# p0rx-001.net
KiCad netlist of a schematic drawn in EAGLE
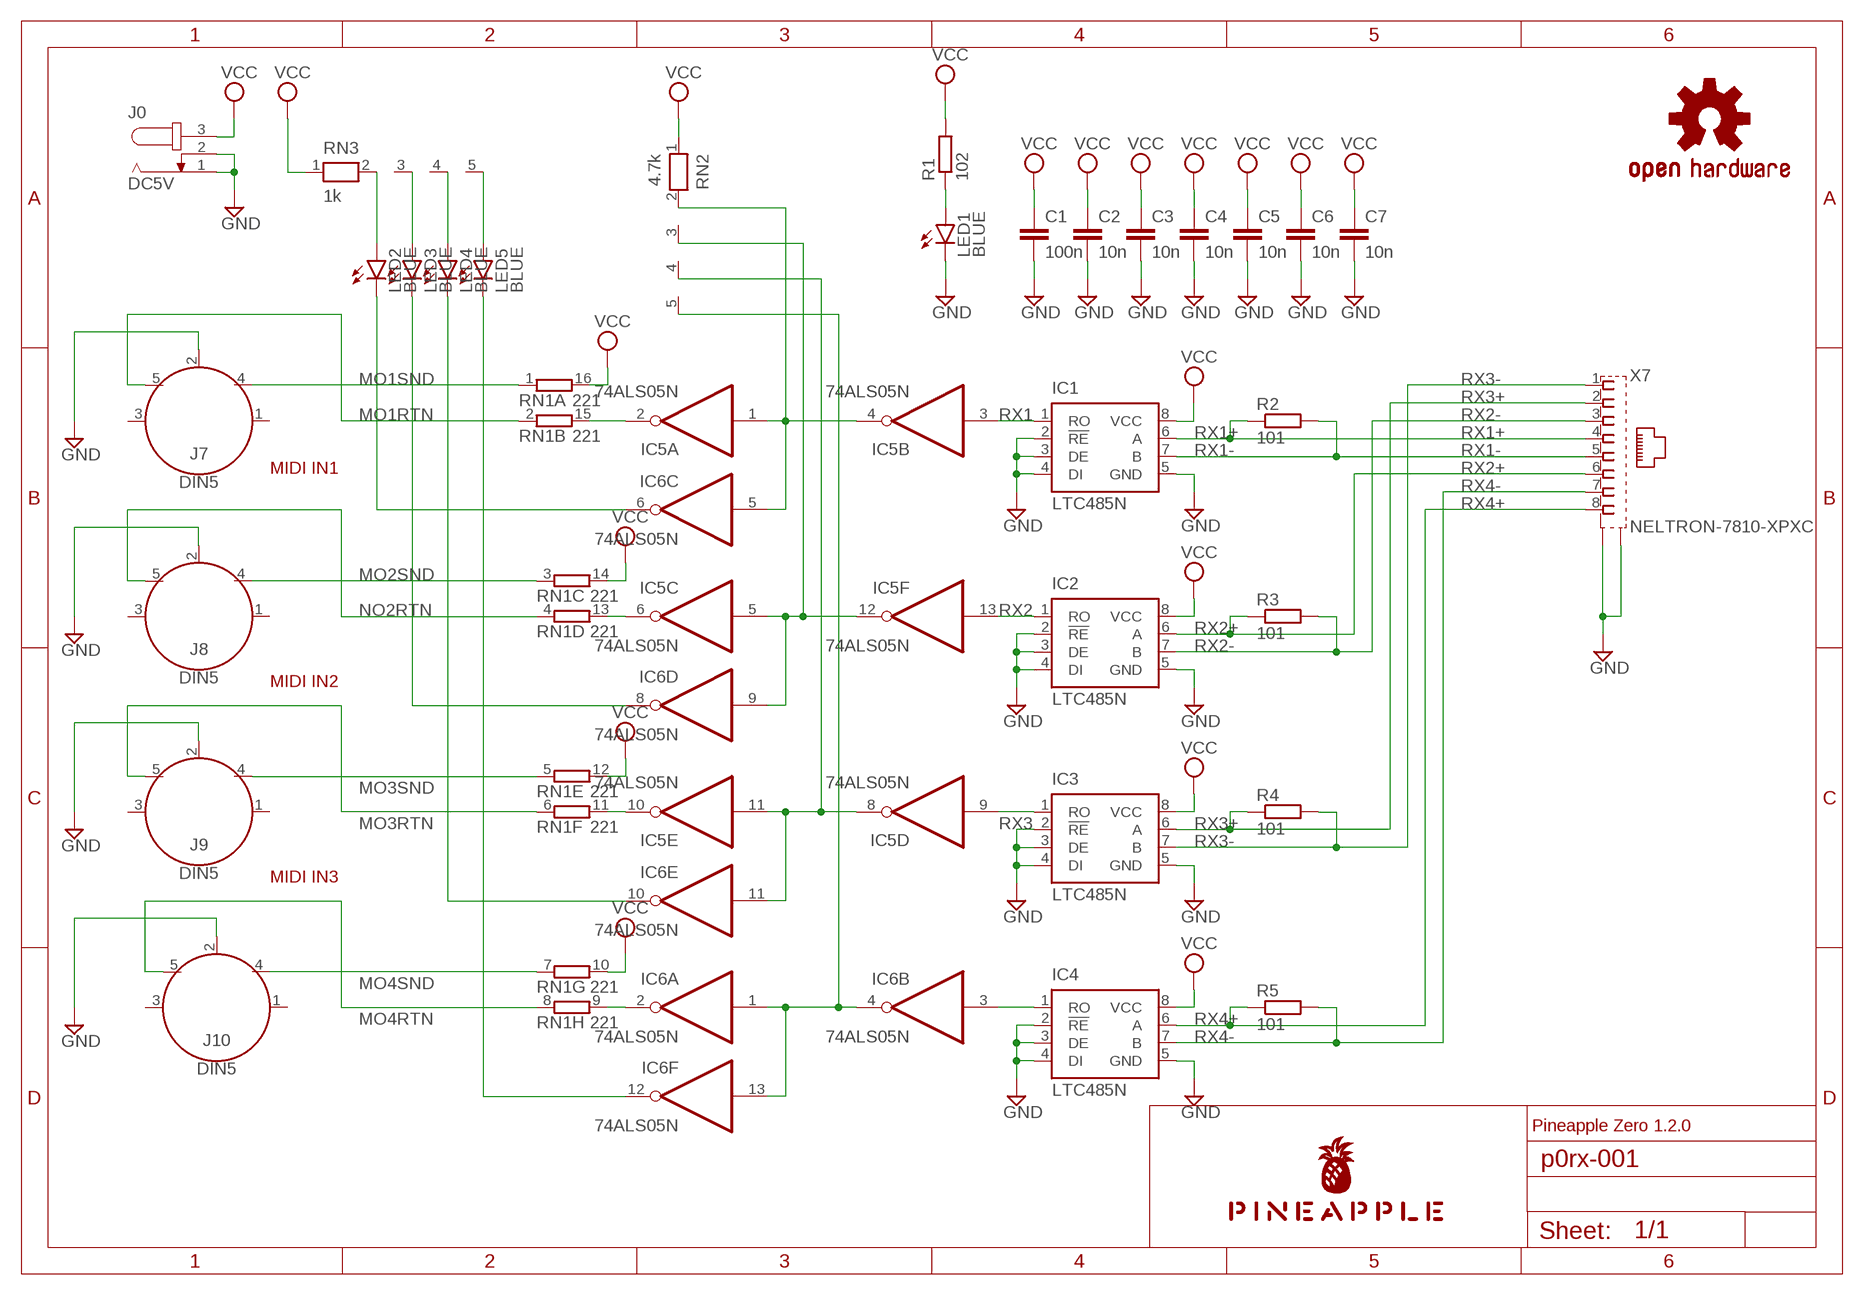
[diagram p0: schematic, sheet 1]

(export (version "E")
  (design (tool "Eeschema 10.0.6"))
  (components
    (comp (ref "C1")
      (value "100n")
      (footprint "eagle-import:C025-024X044")
      (libsource (lib "eagle-import") (part "C-EU025-024X044"))
    )
    (comp (ref "C2")
      (value "10n")
      (footprint "eagle-import:C025-024X044")
      (libsource (lib "eagle-import") (part "C-EU025-024X044"))
    )
    (comp (ref "C3")
      (value "10n")
      (footprint "eagle-import:C025-024X044")
      (libsource (lib "eagle-import") (part "C-EU025-024X044"))
    )
    (comp (ref "C4")
      (value "10n")
      (footprint "eagle-import:C025-024X044")
      (libsource (lib "eagle-import") (part "C-EU025-024X044"))
    )
    (comp (ref "C5")
      (value "10n")
      (footprint "eagle-import:C025-024X044")
      (libsource (lib "eagle-import") (part "C-EU025-024X044"))
    )
    (comp (ref "C6")
      (value "10n")
      (footprint "eagle-import:C025-024X044")
      (libsource (lib "eagle-import") (part "C-EU025-024X044"))
    )
    (comp (ref "C7")
      (value "10n")
      (footprint "eagle-import:C025-024X044")
      (libsource (lib "eagle-import") (part "C-EU025-024X044"))
    )
    (comp (ref "IC1")
      (value "LTC485N")
      (footprint "eagle-import:DIL08")
      (libsource (lib "eagle-import") (part "LTC485N"))
    )
    (comp (ref "IC2")
      (value "LTC485N")
      (footprint "eagle-import:DIL08")
      (libsource (lib "eagle-import") (part "LTC485N"))
    )
    (comp (ref "IC3")
      (value "LTC485N")
      (footprint "eagle-import:DIL08")
      (libsource (lib "eagle-import") (part "LTC485N"))
    )
    (comp (ref "IC4")
      (value "LTC485N")
      (footprint "eagle-import:DIL08")
      (libsource (lib "eagle-import") (part "LTC485N"))
    )
    (comp (ref "IC5")
      (value "74ALS05N")
      (footprint "eagle-import:DIL14")
      (libsource (lib "eagle-import") (part "7405NALS"))
    )
    (comp (ref "IC6")
      (value "74ALS05N")
      (footprint "eagle-import:DIL14")
      (libsource (lib "eagle-import") (part "7405NALS"))
    )
    (comp (ref "J0")
      (value "DC5V")
      (footprint "eagle-import:SPC4077")
      (libsource (lib "eagle-import") (part "JACK-PLUG0"))
    )
    (comp (ref "J7")
      (value "DIN5")
      (footprint "eagle-import:DIN5-RA-PTH")
      (libsource (lib "eagle-import") (part "DIN5"))
    )
    (comp (ref "J8")
      (value "DIN5")
      (footprint "eagle-import:DIN5-RA-PTH")
      (libsource (lib "eagle-import") (part "DIN5"))
    )
    (comp (ref "J9")
      (value "DIN5")
      (footprint "eagle-import:DIN5-RA-PTH")
      (libsource (lib "eagle-import") (part "DIN5"))
    )
    (comp (ref "J10")
      (value "DIN5")
      (footprint "eagle-import:DIN5-RA-PTH")
      (libsource (lib "eagle-import") (part "DIN5"))
    )
    (comp (ref "LED1")
      (value "BLUE")
      (footprint "eagle-import:LED3MM")
      (libsource (lib "eagle-import") (part "LED3MM"))
    )
    (comp (ref "LED2")
      (value "BLUE")
      (footprint "eagle-import:LED3MM")
      (libsource (lib "eagle-import") (part "LED3MM"))
    )
    (comp (ref "LED3")
      (value "BLUE")
      (footprint "eagle-import:LED3MM")
      (libsource (lib "eagle-import") (part "LED3MM"))
    )
    (comp (ref "LED4")
      (value "BLUE")
      (footprint "eagle-import:LED3MM")
      (libsource (lib "eagle-import") (part "LED3MM"))
    )
    (comp (ref "LED5")
      (value "BLUE")
      (footprint "eagle-import:LED3MM")
      (libsource (lib "eagle-import") (part "LED3MM"))
    )
    (comp (ref "LOGO1")
      (value "OSHW-LOGOS-COPPER")
      (footprint "eagle-import:OSHW-LOGO-S_COPPER")
      (libsource (lib "eagle-import") (part "OSHW-LOGOS-COPPER"))
    )
    (comp (ref "R1")
      (value "102")
      (footprint "eagle-import:0204_5")
      (libsource (lib "eagle-import") (part "R-EU_0204/5"))
    )
    (comp (ref "R2")
      (value "101")
      (footprint "eagle-import:0204_5")
      (libsource (lib "eagle-import") (part "R-EU_0204/5"))
    )
    (comp (ref "R3")
      (value "101")
      (footprint "eagle-import:0204_5")
      (libsource (lib "eagle-import") (part "R-EU_0204/5"))
    )
    (comp (ref "R4")
      (value "101")
      (footprint "eagle-import:0204_5")
      (libsource (lib "eagle-import") (part "R-EU_0204/5"))
    )
    (comp (ref "R5")
      (value "101")
      (footprint "eagle-import:0204_5")
      (libsource (lib "eagle-import") (part "R-EU_0204/5"))
    )
    (comp (ref "RN1")
      (value "221")
      (footprint "eagle-import:DIL16")
      (libsource (lib "eagle-import") (part "8R-N"))
    )
    (comp (ref "RN2")
      (value "4.7k")
      (footprint "eagle-import:RN-5")
      (libsource (lib "eagle-import") (part "RN04"))
    )
    (comp (ref "RN3")
      (value "1k")
      (footprint "eagle-import:RN-5")
      (libsource (lib "eagle-import") (part "RN04"))
    )
    (comp (ref "U$1")
      (value "PINEAPPLE450")
      (footprint "eagle-import:PINEAPPLE450")
      (libsource (lib "eagle-import") (part "PINEAPPLE450"))
    )
    (comp (ref "X7")
      (value "NELTRON-7810-XPXC")
      (footprint "eagle-import:NELTRON-7810-XPXC-FOOTPRINT")
      (libsource (lib "eagle-import") (part "NELTRON-7810-XPXC"))
    )
  )
  (nets
    (net (code "1") (name "/MO1RTN") (class "Default")
      (node (ref "J7") (pin "5") (pinfunction "5_5") (pintype "bidirectional"))
      (node (ref "RN1") (pin "2") (pinfunction "1_2") (pintype "passive"))
    )
    (net (code "2") (name "/MO1SND") (class "Default")
      (node (ref "J7") (pin "4") (pinfunction "4_4") (pintype "bidirectional"))
      (node (ref "RN1") (pin "1") (pinfunction "1_1") (pintype "passive"))
    )
    (net (code "3") (name "/MO2SND") (class "Default")
      (node (ref "J8") (pin "4") (pinfunction "4_4") (pintype "bidirectional"))
      (node (ref "RN1") (pin "3") (pinfunction "1_3") (pintype "passive"))
    )
    (net (code "4") (name "/MO3RTN") (class "Default")
      (node (ref "J9") (pin "5") (pinfunction "5_5") (pintype "bidirectional"))
      (node (ref "RN1") (pin "6") (pinfunction "1_6") (pintype "passive"))
    )
    (net (code "5") (name "/MO3SND") (class "Default")
      (node (ref "J9") (pin "4") (pinfunction "4_4") (pintype "bidirectional"))
      (node (ref "RN1") (pin "5") (pinfunction "1_5") (pintype "passive"))
    )
    (net (code "6") (name "/MO4RTN") (class "Default")
      (node (ref "J10") (pin "5") (pinfunction "5_5") (pintype "bidirectional"))
      (node (ref "RN1") (pin "8") (pinfunction "1_8") (pintype "passive"))
    )
    (net (code "7") (name "/MO4SND") (class "Default")
      (node (ref "J10") (pin "4") (pinfunction "4_4") (pintype "bidirectional"))
      (node (ref "RN1") (pin "7") (pinfunction "1_7") (pintype "passive"))
    )
    (net (code "8") (name "/NO2RTN") (class "Default")
      (node (ref "J8") (pin "5") (pinfunction "5_5") (pintype "bidirectional"))
      (node (ref "RN1") (pin "4") (pinfunction "1_4") (pintype "passive"))
    )
    (net (code "9") (name "/RX1") (class "Default")
      (node (ref "IC1") (pin "1") (pinfunction "RO_1") (pintype "output"))
      (node (ref "IC5") (pin "3") (pinfunction "I_3") (pintype "input"))
    )
    (net (code "10") (name "/RX1+") (class "Default")
      (node (ref "IC1") (pin "6") (pinfunction "A_6") (pintype "bidirectional"))
      (node (ref "R2") (pin "1") (pinfunction "1_1") (pintype "passive"))
      (node (ref "X7") (pin "4") (pinfunction "4_4") (pintype "passive"))
    )
    (net (code "11") (name "/RX1-") (class "Default")
      (node (ref "IC1") (pin "7") (pinfunction "B_7") (pintype "bidirectional"))
      (node (ref "R2") (pin "2") (pinfunction "2_2") (pintype "passive"))
      (node (ref "X7") (pin "5") (pinfunction "5_5") (pintype "passive"))
    )
    (net (code "12") (name "/RX2") (class "Default")
      (node (ref "IC2") (pin "1") (pinfunction "RO_1") (pintype "output"))
      (node (ref "IC5") (pin "13") (pinfunction "I_13") (pintype "input"))
    )
    (net (code "13") (name "/RX2+") (class "Default")
      (node (ref "IC2") (pin "6") (pinfunction "A_6") (pintype "bidirectional"))
      (node (ref "R3") (pin "1") (pinfunction "1_1") (pintype "passive"))
      (node (ref "X7") (pin "6") (pinfunction "6_6") (pintype "passive"))
    )
    (net (code "14") (name "/RX2-") (class "Default")
      (node (ref "IC2") (pin "7") (pinfunction "B_7") (pintype "bidirectional"))
      (node (ref "R3") (pin "2") (pinfunction "2_2") (pintype "passive"))
      (node (ref "X7") (pin "3") (pinfunction "3_3") (pintype "passive"))
    )
    (net (code "15") (name "/RX3") (class "Default")
      (node (ref "IC3") (pin "1") (pinfunction "RO_1") (pintype "output"))
      (node (ref "IC5") (pin "9") (pinfunction "I_9") (pintype "input"))
    )
    (net (code "16") (name "/RX3+") (class "Default")
      (node (ref "IC3") (pin "6") (pinfunction "A_6") (pintype "bidirectional"))
      (node (ref "R4") (pin "1") (pinfunction "1_1") (pintype "passive"))
      (node (ref "X7") (pin "2") (pinfunction "2_2") (pintype "passive"))
    )
    (net (code "17") (name "/RX3-") (class "Default")
      (node (ref "IC3") (pin "7") (pinfunction "B_7") (pintype "bidirectional"))
      (node (ref "R4") (pin "2") (pinfunction "2_2") (pintype "passive"))
      (node (ref "X7") (pin "1") (pinfunction "1_1") (pintype "passive"))
    )
    (net (code "18") (name "/RX4+") (class "Default")
      (node (ref "IC4") (pin "6") (pinfunction "A_6") (pintype "bidirectional"))
      (node (ref "R5") (pin "1") (pinfunction "1_1") (pintype "passive"))
      (node (ref "X7") (pin "8") (pinfunction "8_8") (pintype "passive"))
    )
    (net (code "19") (name "/RX4-") (class "Default")
      (node (ref "IC4") (pin "7") (pinfunction "B_7") (pintype "bidirectional"))
      (node (ref "R5") (pin "2") (pinfunction "2_2") (pintype "passive"))
      (node (ref "X7") (pin "7") (pinfunction "7_7") (pintype "passive"))
    )
    (net (code "20") (name "GND") (class "Default")
      (node (ref "C1") (pin "2") (pinfunction "2_2") (pintype "passive"))
      (node (ref "C2") (pin "2") (pinfunction "2_2") (pintype "passive"))
      (node (ref "C3") (pin "2") (pinfunction "2_2") (pintype "passive"))
      (node (ref "C4") (pin "2") (pinfunction "2_2") (pintype "passive"))
      (node (ref "C5") (pin "2") (pinfunction "2_2") (pintype "passive"))
      (node (ref "C6") (pin "2") (pinfunction "2_2") (pintype "passive"))
      (node (ref "C7") (pin "2") (pinfunction "2_2") (pintype "passive"))
      (node (ref "IC1") (pin "2") (pinfunction "~{RE}_2") (pintype "input"))
      (node (ref "IC1") (pin "3") (pinfunction "DE_3") (pintype "input"))
      (node (ref "IC1") (pin "4") (pinfunction "DI_4") (pintype "input"))
      (node (ref "IC1") (pin "5") (pinfunction "GND_5") (pintype "input"))
      (node (ref "IC2") (pin "2") (pinfunction "~{RE}_2") (pintype "input"))
      (node (ref "IC2") (pin "3") (pinfunction "DE_3") (pintype "input"))
      (node (ref "IC2") (pin "4") (pinfunction "DI_4") (pintype "input"))
      (node (ref "IC2") (pin "5") (pinfunction "GND_5") (pintype "input"))
      (node (ref "IC3") (pin "2") (pinfunction "~{RE}_2") (pintype "input"))
      (node (ref "IC3") (pin "3") (pinfunction "DE_3") (pintype "input"))
      (node (ref "IC3") (pin "4") (pinfunction "DI_4") (pintype "input"))
      (node (ref "IC3") (pin "5") (pinfunction "GND_5") (pintype "input"))
      (node (ref "IC4") (pin "2") (pinfunction "~{RE}_2") (pintype "input"))
      (node (ref "IC4") (pin "3") (pinfunction "DE_3") (pintype "input"))
      (node (ref "IC4") (pin "4") (pinfunction "DI_4") (pintype "input"))
      (node (ref "IC4") (pin "5") (pinfunction "GND_5") (pintype "input"))
      (node (ref "J0") (pin "1") (pinfunction "1_1") (pintype "passive"))
      (node (ref "J0") (pin "2") (pinfunction "2_2") (pintype "passive"))
      (node (ref "J10") (pin "2") (pinfunction "2_2") (pintype "bidirectional"))
      (node (ref "J7") (pin "2") (pinfunction "2_2") (pintype "bidirectional"))
      (node (ref "J8") (pin "2") (pinfunction "2_2") (pintype "bidirectional"))
      (node (ref "J9") (pin "2") (pinfunction "2_2") (pintype "bidirectional"))
      (node (ref "LED1") (pin "K") (pinfunction "C_K") (pintype "passive"))
      (node (ref "X7") (pin "S1") (pinfunction "S1_S1") (pintype "passive"))
      (node (ref "X7") (pin "S2") (pinfunction "S2_S2") (pintype "passive"))
    )
    (net (code "21") (name "Net-(IC4-RO)") (class "Default")
      (node (ref "IC4") (pin "1") (pinfunction "RO_1") (pintype "output"))
      (node (ref "IC6") (pin "3") (pinfunction "I_3") (pintype "input"))
    )
    (net (code "22") (name "Net-(IC5A-I)") (class "Default")
      (node (ref "IC5") (pin "1") (pinfunction "I_1") (pintype "input"))
      (node (ref "IC5") (pin "4") (pinfunction "O_4") (pintype "open_collector"))
      (node (ref "IC6") (pin "5") (pinfunction "I_5") (pintype "input"))
      (node (ref "RN2") (pin "2") (pinfunction "2_2") (pintype "passive"))
    )
    (net (code "23") (name "Net-(IC5A-O)") (class "Default")
      (node (ref "IC5") (pin "2") (pinfunction "O_2") (pintype "open_collector"))
      (node (ref "RN1") (pin "15") (pinfunction "2_15") (pintype "passive"))
    )
    (net (code "24") (name "Net-(IC5C-I)") (class "Default")
      (node (ref "IC5") (pin "12") (pinfunction "O_12") (pintype "open_collector"))
      (node (ref "IC5") (pin "5") (pinfunction "I_5") (pintype "input"))
      (node (ref "IC6") (pin "9") (pinfunction "I_9") (pintype "input"))
      (node (ref "RN2") (pin "3") (pinfunction "3_3") (pintype "passive"))
    )
    (net (code "25") (name "Net-(IC5C-O)") (class "Default")
      (node (ref "IC5") (pin "6") (pinfunction "O_6") (pintype "open_collector"))
      (node (ref "RN1") (pin "13") (pinfunction "2_13") (pintype "passive"))
    )
    (net (code "26") (name "Net-(IC5D-O)") (class "Default")
      (node (ref "IC5") (pin "11") (pinfunction "I_11") (pintype "input"))
      (node (ref "IC5") (pin "8") (pinfunction "O_8") (pintype "open_collector"))
      (node (ref "IC6") (pin "11") (pinfunction "I_11") (pintype "input"))
      (node (ref "RN2") (pin "4") (pinfunction "4_4") (pintype "passive"))
    )
    (net (code "27") (name "Net-(IC5E-O)") (class "Default")
      (node (ref "IC5") (pin "10") (pinfunction "O_10") (pintype "open_collector"))
      (node (ref "RN1") (pin "11") (pinfunction "2_11") (pintype "passive"))
    )
    (net (code "28") (name "Net-(IC6A-I)") (class "Default")
      (node (ref "IC6") (pin "1") (pinfunction "I_1") (pintype "input"))
      (node (ref "IC6") (pin "13") (pinfunction "I_13") (pintype "input"))
      (node (ref "IC6") (pin "4") (pinfunction "O_4") (pintype "open_collector"))
      (node (ref "RN2") (pin "5") (pinfunction "5_5") (pintype "passive"))
    )
    (net (code "29") (name "Net-(IC6A-O)") (class "Default")
      (node (ref "IC6") (pin "2") (pinfunction "O_2") (pintype "open_collector"))
      (node (ref "RN1") (pin "9") (pinfunction "2_9") (pintype "passive"))
    )
    (net (code "30") (name "Net-(IC6C-O)") (class "Default")
      (node (ref "IC6") (pin "6") (pinfunction "O_6") (pintype "open_collector"))
      (node (ref "LED2") (pin "K") (pinfunction "C_K") (pintype "passive"))
    )
    (net (code "31") (name "Net-(IC6D-O)") (class "Default")
      (node (ref "IC6") (pin "8") (pinfunction "O_8") (pintype "open_collector"))
      (node (ref "LED3") (pin "K") (pinfunction "C_K") (pintype "passive"))
    )
    (net (code "32") (name "Net-(IC6E-O)") (class "Default")
      (node (ref "IC6") (pin "10") (pinfunction "O_10") (pintype "open_collector"))
      (node (ref "LED4") (pin "K") (pinfunction "C_K") (pintype "passive"))
    )
    (net (code "33") (name "Net-(IC6F-O)") (class "Default")
      (node (ref "IC6") (pin "12") (pinfunction "O_12") (pintype "open_collector"))
      (node (ref "LED5") (pin "K") (pinfunction "C_K") (pintype "passive"))
    )
    (net (code "34") (name "Net-(LED1-PadA)") (class "Default")
      (node (ref "LED1") (pin "A") (pinfunction "A_A") (pintype "passive"))
      (node (ref "R1") (pin "1") (pinfunction "1_1") (pintype "passive"))
    )
    (net (code "35") (name "Net-(LED2-PadA)") (class "Default")
      (node (ref "LED2") (pin "A") (pinfunction "A_A") (pintype "passive"))
      (node (ref "RN3") (pin "2") (pinfunction "2_2") (pintype "passive"))
    )
    (net (code "36") (name "Net-(LED3-PadA)") (class "Default")
      (node (ref "LED3") (pin "A") (pinfunction "A_A") (pintype "passive"))
      (node (ref "RN3") (pin "3") (pinfunction "3_3") (pintype "passive"))
    )
    (net (code "37") (name "Net-(LED4-PadA)") (class "Default")
      (node (ref "LED4") (pin "A") (pinfunction "A_A") (pintype "passive"))
      (node (ref "RN3") (pin "4") (pinfunction "4_4") (pintype "passive"))
    )
    (net (code "38") (name "Net-(LED5-PadA)") (class "Default")
      (node (ref "LED5") (pin "A") (pinfunction "A_A") (pintype "passive"))
      (node (ref "RN3") (pin "5") (pinfunction "5_5") (pintype "passive"))
    )
    (net (code "39") (name "VCC") (class "Default")
      (node (ref "C1") (pin "1") (pinfunction "1_1") (pintype "passive"))
      (node (ref "C2") (pin "1") (pinfunction "1_1") (pintype "passive"))
      (node (ref "C3") (pin "1") (pinfunction "1_1") (pintype "passive"))
      (node (ref "C4") (pin "1") (pinfunction "1_1") (pintype "passive"))
      (node (ref "C5") (pin "1") (pinfunction "1_1") (pintype "passive"))
      (node (ref "C6") (pin "1") (pinfunction "1_1") (pintype "passive"))
      (node (ref "C7") (pin "1") (pinfunction "1_1") (pintype "passive"))
      (node (ref "IC1") (pin "8") (pinfunction "VCC_8") (pintype "input"))
      (node (ref "IC2") (pin "8") (pinfunction "VCC_8") (pintype "input"))
      (node (ref "IC3") (pin "8") (pinfunction "VCC_8") (pintype "input"))
      (node (ref "IC4") (pin "8") (pinfunction "VCC_8") (pintype "input"))
      (node (ref "J0") (pin "3") (pinfunction "3_3") (pintype "passive"))
      (node (ref "R1") (pin "2") (pinfunction "2_2") (pintype "passive"))
      (node (ref "RN1") (pin "10") (pinfunction "2_10") (pintype "passive"))
      (node (ref "RN1") (pin "12") (pinfunction "2_12") (pintype "passive"))
      (node (ref "RN1") (pin "14") (pinfunction "2_14") (pintype "passive"))
      (node (ref "RN1") (pin "16") (pinfunction "2_16") (pintype "passive"))
      (node (ref "RN2") (pin "1") (pinfunction "1_1") (pintype "passive"))
      (node (ref "RN3") (pin "1") (pinfunction "1_1") (pintype "passive"))
    )
    (net (code "40") (name "unconnected-(J7-Pad1)") (class "Default")
      (node (ref "J7") (pin "1") (pinfunction "1_1") (pintype "bidirectional"))
    )
    (net (code "41") (name "unconnected-(J7-Pad3)") (class "Default")
      (node (ref "J7") (pin "3") (pinfunction "3_3") (pintype "bidirectional"))
    )
    (net (code "42") (name "unconnected-(J8-Pad1)") (class "Default")
      (node (ref "J8") (pin "1") (pinfunction "1_1") (pintype "bidirectional"))
    )
    (net (code "43") (name "unconnected-(J8-Pad3)") (class "Default")
      (node (ref "J8") (pin "3") (pinfunction "3_3") (pintype "bidirectional"))
    )
    (net (code "44") (name "unconnected-(J9-Pad1)") (class "Default")
      (node (ref "J9") (pin "1") (pinfunction "1_1") (pintype "bidirectional"))
    )
    (net (code "45") (name "unconnected-(J9-Pad3)") (class "Default")
      (node (ref "J9") (pin "3") (pinfunction "3_3") (pintype "bidirectional"))
    )
    (net (code "46") (name "unconnected-(J10-Pad1)") (class "Default")
      (node (ref "J10") (pin "1") (pinfunction "1_1") (pintype "bidirectional"))
    )
    (net (code "47") (name "unconnected-(J10-Pad3)") (class "Default")
      (node (ref "J10") (pin "3") (pinfunction "3_3") (pintype "bidirectional"))
    )
  )
)
